# Sheet_1_2024-04-15.net
KiCad netlist of a schematic drawn in Altium Designer
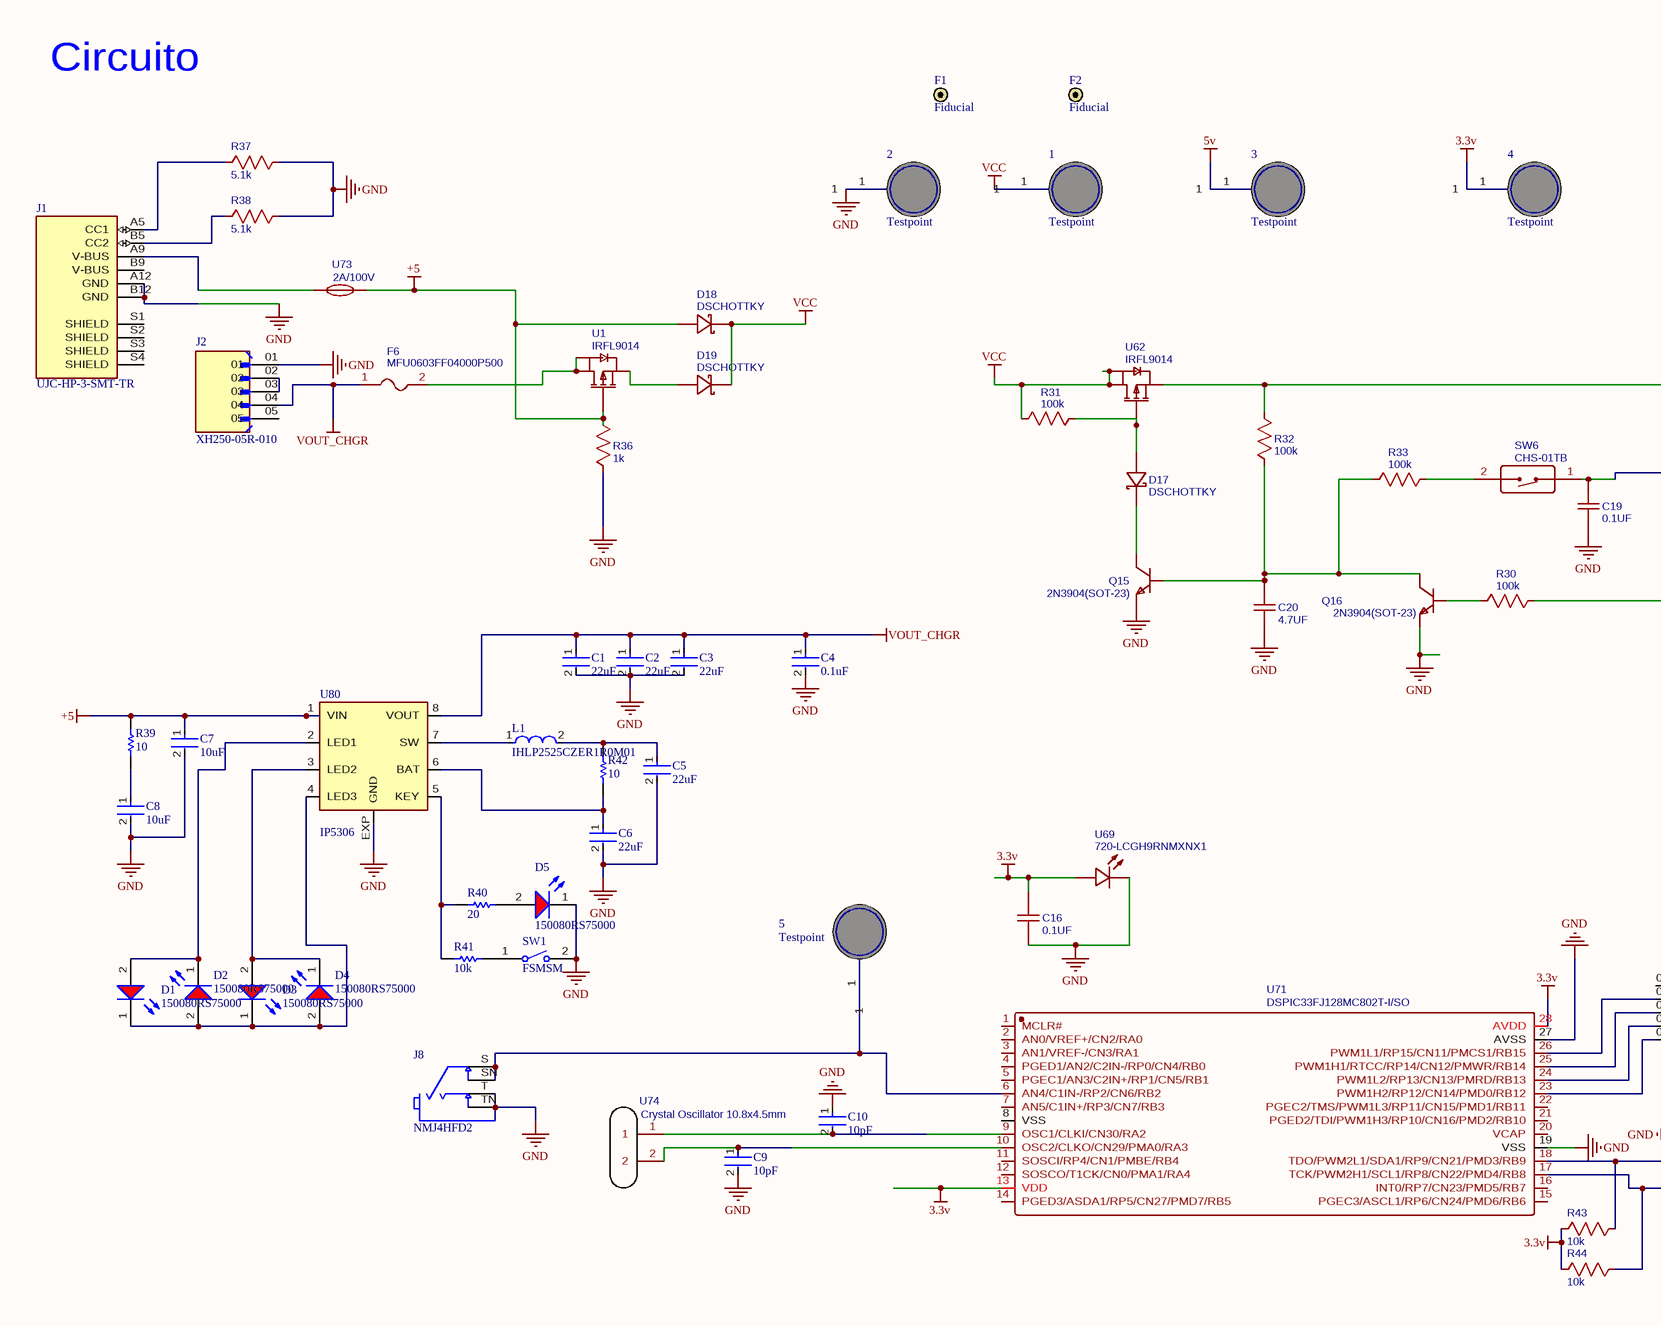
[diagram p0: Sheet_1_2024-04-15.schdoc, left]
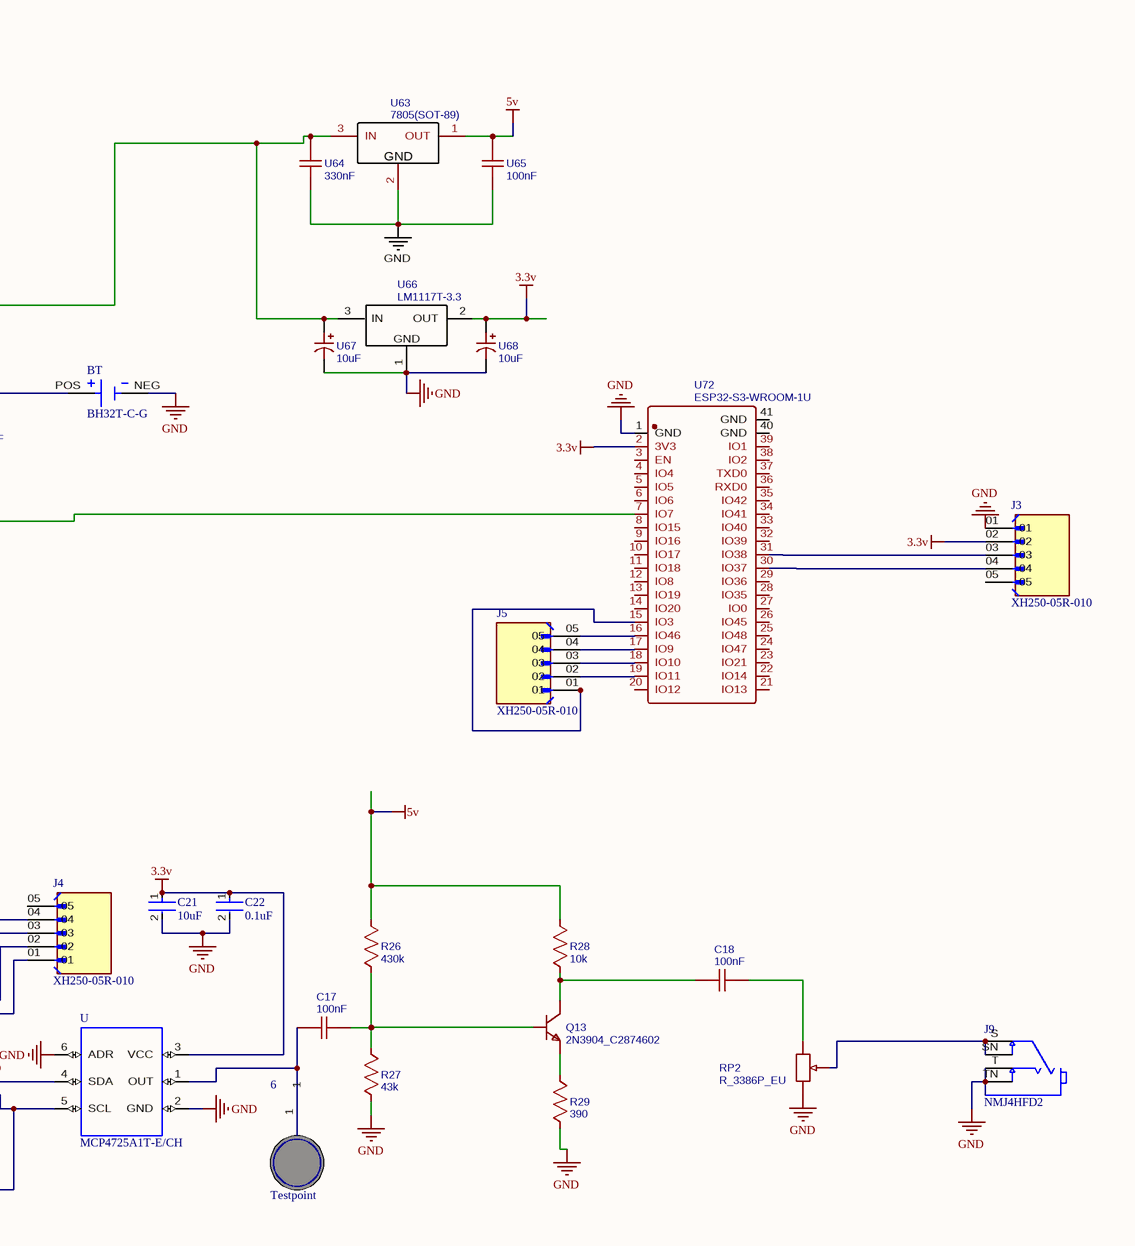
[diagram p1: Sheet_1_2024-04-15.schdoc, right]

(export (version "E")
  (design (tool "Eeschema 10.0.6"))
  (components
    (comp (ref "1")
      (value "Testpoint")
      (footprint "TestPoint")
      (libsource (lib "Schlib1") (part "Testpoint"))
    )
    (comp (ref "2")
      (value "Testpoint")
      (footprint "TestPoint")
      (libsource (lib "Schlib1") (part "Testpoint"))
    )
    (comp (ref "3")
      (value "Testpoint")
      (footprint "TestPoint")
      (libsource (lib "Schlib1") (part "Testpoint"))
    )
    (comp (ref "4")
      (value "Testpoint")
      (footprint "TestPoint")
      (libsource (lib "Schlib1") (part "Testpoint"))
    )
    (comp (ref "5")
      (value "Testpoint")
      (footprint "TestPoint")
      (libsource (lib "Schlib1") (part "Testpoint"))
    )
    (comp (ref "6")
      (value "Testpoint")
      (footprint "TestPoint")
      (libsource (lib "Schlib1") (part "Testpoint"))
    )
    (comp (ref "BT")
      (value "BH32T-C-G")
      (footprint "PcbLib1:BAT_BH32T-C-G")
      (description "BATTERY HOLDER COIN 20MM PC PIN")
      (fields (field (name "MF") "MPD"))
      (libsource (lib "Schlib1") (part "BH32T-C-G"))
    )
    (comp (ref "C1")
      (value "22uF")
      (footprint "FP-C0805C-DN-MFG")
      (description "Capacitor; Ceramic; Cap; 22.0pF; Tol 5%; SMT; Vol-Rtg 50V; C0G; Tape and Reel")
      (fields
        (field (name "OCTOPART") "https://octopart.com/c0805c220j5gactu-kemet-145470")
        (field (name "MANUFACTURER") "KEMET")
      )
      (libsource (lib "Altium Content Vault") (part "b4654b650e69147ec39a6b967a45e02"))
    )
    (comp (ref "C2")
      (value "22uF")
      (footprint "FP-C0805C-DN-MFG")
      (description "Capacitor; Ceramic; Cap; 22.0pF; Tol 5%; SMT; Vol-Rtg 50V; C0G; Tape and Reel")
      (fields
        (field (name "OCTOPART") "https://octopart.com/c0805c220j5gactu-kemet-145470")
        (field (name "MANUFACTURER") "KEMET")
      )
      (libsource (lib "Altium Content Vault") (part "b4654b650e69147ec39a6b967a45e02"))
    )
    (comp (ref "C3")
      (value "22uF")
      (footprint "FP-C0805C-DN-MFG")
      (description "Capacitor; Ceramic; Cap; 22.0pF; Tol 5%; SMT; Vol-Rtg 50V; C0G; Tape and Reel")
      (fields
        (field (name "OCTOPART") "https://octopart.com/c0805c220j5gactu-kemet-145470")
        (field (name "MANUFACTURER") "KEMET")
      )
      (libsource (lib "Altium Content Vault") (part "b4654b650e69147ec39a6b967a45e02"))
    )
    (comp (ref "C4")
      (value "0.1uF")
      (footprint "FP-C0805C-DN-MFG")
      (description "Capacitor; Ceramic; Cap; 22.0pF; Tol 5%; SMT; Vol-Rtg 50V; C0G; Tape and Reel")
      (fields
        (field (name "OCTOPART") "https://octopart.com/c0805c220j5gactu-kemet-145470")
        (field (name "MANUFACTURER") "KEMET")
      )
      (libsource (lib "Altium Content Vault") (part "b4654b650e69147ec39a6b967a45e02"))
    )
    (comp (ref "C5")
      (value "22uF")
      (footprint "FP-C0805C-DN-MFG")
      (description "Capacitor; Ceramic; Cap; 22.0pF; Tol 5%; SMT; Vol-Rtg 50V; C0G; Tape and Reel")
      (fields
        (field (name "OCTOPART") "https://octopart.com/c0805c220j5gactu-kemet-145470")
        (field (name "MANUFACTURER") "KEMET")
      )
      (libsource (lib "Altium Content Vault") (part "b4654b650e69147ec39a6b967a45e02"))
    )
    (comp (ref "C6")
      (value "22uF")
      (footprint "FP-C0805C-DN-MFG")
      (description "Capacitor; Ceramic; Cap; 22.0pF; Tol 5%; SMT; Vol-Rtg 50V; C0G; Tape and Reel")
      (fields
        (field (name "OCTOPART") "https://octopart.com/c0805c220j5gactu-kemet-145470")
        (field (name "MANUFACTURER") "KEMET")
      )
      (libsource (lib "Altium Content Vault") (part "b4654b650e69147ec39a6b967a45e02"))
    )
    (comp (ref "C7")
      (value "10uF")
      (footprint "FP-C0805C-DN-MFG")
      (description "Capacitor; Ceramic; Cap; 22.0pF; Tol 5%; SMT; Vol-Rtg 50V; C0G; Tape and Reel")
      (fields
        (field (name "OCTOPART") "https://octopart.com/c0805c220j5gactu-kemet-145470")
        (field (name "MANUFACTURER") "KEMET")
      )
      (libsource (lib "Altium Content Vault") (part "b4654b650e69147ec39a6b967a45e02"))
    )
    (comp (ref "C8")
      (value "10uF")
      (footprint "FP-C0805C-DN-MFG")
      (description "Capacitor; Ceramic; Cap; 22.0pF; Tol 5%; SMT; Vol-Rtg 50V; C0G; Tape and Reel")
      (fields
        (field (name "OCTOPART") "https://octopart.com/c0805c220j5gactu-kemet-145470")
        (field (name "MANUFACTURER") "KEMET")
      )
      (libsource (lib "Altium Content Vault") (part "b4654b650e69147ec39a6b967a45e02"))
    )
    (comp (ref "C9")
      (value "10pF")
      (footprint "FP-C0805C-DN-MFG")
      (description "Capacitor; Ceramic; Cap; 22.0pF; Tol 5%; SMT; Vol-Rtg 50V; C0G; Tape and Reel")
      (fields
        (field (name "OCTOPART") "https://octopart.com/c0805c220j5gactu-kemet-145470")
        (field (name "MANUFACTURER") "KEMET")
      )
      (libsource (lib "Altium Content Vault") (part "b4654b650e69147ec39a6b967a45e02"))
    )
    (comp (ref "C10")
      (value "10pF")
      (footprint "FP-C0805C-DN-MFG")
      (description "Capacitor; Ceramic; Cap; 22.0pF; Tol 5%; SMT; Vol-Rtg 50V; C0G; Tape and Reel")
      (fields
        (field (name "OCTOPART") "https://octopart.com/c0805c220j5gactu-kemet-145470")
        (field (name "MANUFACTURER") "KEMET")
      )
      (libsource (lib "Altium Content Vault") (part "b4654b650e69147ec39a6b967a45e02"))
    )
    (comp (ref "C16")
      (value "0.1UF")
      (footprint "PcbLib1:RESC2012X60N")
      (fields
        (field (name "MANUFACTURER") "ReliaPro")
        (field (name "MANUFACTURER PART") "250V 0.1UF 5% CBBCapacitor")
      )
      (libsource (lib "altium-import") (part "root_1_0.1UF_"))
    )
    (comp (ref "C17")
      (value "100nF")
      (footprint "PcbLib1:RESC2012X60N")
      (fields (field (name "CONTRIBUTOR") "LCEDA_Lib"))
      (libsource (lib "altium-import") (part "root_0_100nF_"))
    )
    (comp (ref "C18")
      (value "100nF")
      (footprint "PcbLib1:RESC2012X60N")
      (fields (field (name "CONTRIBUTOR") "LCEDA_Lib"))
      (libsource (lib "altium-import") (part "root_0_100nF_"))
    )
    (comp (ref "C19")
      (value "0.1UF")
      (footprint "PcbLib1:RESC2012X60N")
      (fields
        (field (name "MANUFACTURER") "ReliaPro")
        (field (name "MANUFACTURER PART") "250V 0.1UF 5% CBBCapacitor")
      )
      (libsource (lib "altium-import") (part "root_1_0.1UF_"))
    )
    (comp (ref "C20")
      (value "4.7UF")
      (footprint "PcbLib1:RESC2012X60N")
      (fields
        (field (name "MANUFACTURER") "ReliaPro")
        (field (name "MANUFACTURER PART") "250V 0.1UF 5% CBBCapacitor")
      )
      (libsource (lib "altium-import") (part "root_1_4.7UF_"))
    )
    (comp (ref "C21")
      (value "10uF")
      (footprint "FP-C0805C-DN-MFG")
      (description "Capacitor; Ceramic; Cap; 22.0pF; Tol 5%; SMT; Vol-Rtg 50V; C0G; Tape and Reel")
      (fields
        (field (name "OCTOPART") "https://octopart.com/c0805c220j5gactu-kemet-145470")
        (field (name "MANUFACTURER") "KEMET")
      )
      (libsource (lib "Altium Content Vault") (part "b4654b650e69147ec39a6b967a45e02"))
    )
    (comp (ref "C22")
      (value "0.1uF")
      (footprint "FP-C0805C-DN-MFG")
      (description "Capacitor; Ceramic; Cap; 22.0pF; Tol 5%; SMT; Vol-Rtg 50V; C0G; Tape and Reel")
      (fields
        (field (name "OCTOPART") "https://octopart.com/c0805c220j5gactu-kemet-145470")
        (field (name "MANUFACTURER") "KEMET")
      )
      (libsource (lib "Altium Content Vault") (part "b4654b650e69147ec39a6b967a45e02"))
    )
    (comp (ref "D1")
      (value "150080RS75000")
      (footprint "WL-SMCW_0805_150080xx75000")
      (libsource (lib "Altium Content Vault") (part "LED_Red_2A-1K"))
    )
    (comp (ref "D2")
      (value "150080RS75000")
      (footprint "WL-SMCW_0805_150080xx75000")
      (libsource (lib "Altium Content Vault") (part "LED_Red_2A-1K"))
    )
    (comp (ref "D3")
      (value "150080RS75000")
      (footprint "WL-SMCW_0805_150080xx75000")
      (libsource (lib "Altium Content Vault") (part "LED_Red_2A-1K"))
    )
    (comp (ref "D4")
      (value "150080RS75000")
      (footprint "WL-SMCW_0805_150080xx75000")
      (libsource (lib "Altium Content Vault") (part "LED_Red_2A-1K"))
    )
    (comp (ref "D5")
      (value "150080RS75000")
      (footprint "WL-SMCW_0805_150080xx75000")
      (libsource (lib "Altium Content Vault") (part "LED_Red_2A-1K"))
    )
    (comp (ref "D17")
      (value "DSCHOTTKY")
      (footprint "PcbLib1:SS34BF")
      (fields (field (name "MANUFACTURER PART") "DSchottky") (field (name "CONTRIBUTOR") "LCSC"))
      (libsource (lib "altium-import") (part "root_1_DSCHOTTKY_"))
    )
    (comp (ref "D18")
      (value "DSCHOTTKY")
      (footprint "PcbLib1:SS34BF")
      (fields (field (name "MANUFACTURER PART") "DSchottky") (field (name "CONTRIBUTOR") "LCSC"))
      (libsource (lib "altium-import") (part "root_2_DSCHOTTKY_"))
    )
    (comp (ref "D19")
      (value "DSCHOTTKY")
      (footprint "PcbLib1:SS34BF")
      (fields (field (name "MANUFACTURER PART") "DSchottky") (field (name "CONTRIBUTOR") "LCSC"))
      (libsource (lib "altium-import") (part "root_2_DSCHOTTKY_"))
    )
    (comp (ref "F1") (value "Fiducial") (footprint "Fiducial") (libsource (lib "Schlib1") (part "Fiducial")))
    (comp (ref "F2") (value "Fiducial") (footprint "Fiducial") (libsource (lib "Schlib1") (part "Fiducial")))
    (comp (ref "F6")
      (value "MFU0603FF04000P500")
      (footprint "PcbLib1:RESC2012X60N")
      (fields (field (name "MANUFACTURER") "VISHAY(威世)") (field (name "CONTRIBUTOR") "LCSC"))
      (libsource (lib "altium-import") (part "root_0_MFU0603FF04000P500_"))
    )
    (comp (ref "J1")
      (value "UJC-HP-3-SMT-TR")
      (footprint "PcbLib1:CUI_UJC-HP-3-SMT-TR")
      (description "Type C, 3 A, Right Angle, Surface Mount (SMT), Power-Only USB Receptacle")
      (libsource (lib "Schlib1") (part "UJC-HP-3-SMT-TR"))
    )
    (comp (ref "J2")
      (value "XH250-05R-010")
      (footprint "PcbLib1:VALCON_XH250-05R-010")
      (description "Valcon Wire-to-Board 2.50mm Straight & Right Angle PCB Connectors")
      (fields (field (name "MF") "Valcon"))
      (libsource (lib "") (part "XH250-05R-010_1"))
    )
    (comp (ref "J3")
      (value "XH250-05R-010")
      (footprint "PcbLib1:VALCON_XH250-05R-010 - duplicate")
      (description "Valcon Wire-to-Board 2.50mm Straight & Right Angle PCB Connectors")
      (fields (field (name "MF") "Valcon"))
      (libsource (lib "") (part "XH250-05R-010_2"))
    )
    (comp (ref "J4")
      (value "XH250-05R-010")
      (footprint "PcbLib1:VALCON_XH250-05R-010 - duplicate - duplicate")
      (description "Valcon Wire-to-Board 2.50mm Straight & Right Angle PCB Connectors")
      (fields (field (name "MF") "Valcon"))
      (libsource (lib "") (part "XH250-05R-010_3"))
    )
    (comp (ref "J5")
      (value "XH250-05R-010")
      (footprint "PcbLib1:VALCON_XH250-05R-010 - duplicate")
      (description "Valcon Wire-to-Board 2.50mm Straight & Right Angle PCB Connectors")
      (fields (field (name "MF") "Valcon"))
      (libsource (lib "Schlib1") (part "XH250-05R-010"))
    )
    (comp (ref "J8")
      (value "NMJ4HFD2")
      (footprint "NEUTRIK_NMJ4HFD2")
      (description "1/4 mono jack, switched, with a full threaded nose and straight PCB pins, mounting nut included")
      (fields (field (name "MF") "Neutrik"))
      (libsource (lib "Schlib1") (part "NMJ4HFD2"))
    )
    (comp (ref "J9")
      (value "NMJ4HFD2")
      (footprint "NEUTRIK_NMJ4HFD2")
      (description "1/4 mono jack, switched, with a full threaded nose and straight PCB pins, mounting nut included")
      (fields (field (name "MF") "Neutrik"))
      (libsource (lib "Schlib1") (part "NMJ4HFD2"))
    )
    (comp (ref "L1")
      (value "IHLP2525CZER1R0M01")
      (footprint "FP-IHLP-2525CZ-FP_2_413x3-MFG")
      (description "Commercial Inductors, High Saturation Series 1uH 11A 10mΩ 20%")
      (fields (field (name "TOLERANCE") "20%"))
      (libsource (lib "Altium Content Vault") (part "725321dda6339637d4d059423bc1c3c"))
    )
    (comp (ref "Q13")
      (value "2N3904_C2874602")
      (footprint "PcbLib1:TO92127P495H495-3")
      (fields
        (field (name "MANUFACTURER") "JSMSEMI(杰盛微)")
        (field (name "MANUFACTURER PART") "2N3904")
        (field (name "CONTRIBUTOR") "LCSC")
      )
      (libsource (lib "altium-import") (part "root_0_2N3904_C2874602_"))
    )
    (comp (ref "Q15")
      (value "2N3904(SOT-23)")
      (footprint "PcbLib1:TO92127P495H495-3")
      (fields
        (field (name "MANUFACTURER") "KEC")
        (field (name "MANUFACTURER PART") "2n3904S-RTK/PS")
        (field (name "CONTRIBUTOR") "LCEDA_Lib")
      )
      (libsource (lib "altium-import") (part "root_0_2N3904(SOT-23)_"))
    )
    (comp (ref "Q16")
      (value "2N3904(SOT-23)")
      (footprint "PcbLib1:TO92127P495H495-3 - duplicate")
      (fields
        (field (name "MANUFACTURER") "KEC")
        (field (name "MANUFACTURER PART") "2n3904S-RTK/PS")
        (field (name "CONTRIBUTOR") "LCEDA_Lib")
      )
      (libsource (lib "altium-import") (part "root_0_2N3904(SOT-23)_"))
    )
    (comp (ref "R26")
      (value "430k")
      (footprint "PcbLib1:RESC2012X60N")
      (fields (field (name "CONTRIBUTOR") "LCEDA_Lib"))
      (libsource (lib "altium-import") (part "root_1_430k_"))
    )
    (comp (ref "R27")
      (value "43k")
      (footprint "PcbLib1:RESC2012X60N")
      (fields (field (name "CONTRIBUTOR") "LCEDA_Lib"))
      (libsource (lib "altium-import") (part "root_1_43k_"))
    )
    (comp (ref "R28")
      (value "10k")
      (footprint "PcbLib1:RESC2012X60N")
      (fields (field (name "CONTRIBUTOR") "LCEDA_Lib"))
      (libsource (lib "altium-import") (part "root_1_10k_"))
    )
    (comp (ref "R29")
      (value "390")
      (footprint "PcbLib1:RESC2012X60N")
      (fields (field (name "CONTRIBUTOR") "LCEDA_Lib"))
      (libsource (lib "altium-import") (part "root_1_390_"))
    )
    (comp (ref "R30")
      (value "100k")
      (footprint "PcbLib1:RESC2012X60N")
      (fields (field (name "CONTRIBUTOR") "LCEDA_Lib"))
      (libsource (lib "altium-import") (part "root_0_100k_"))
    )
    (comp (ref "R31")
      (value "100k")
      (footprint "PcbLib1:RESC2012X60N")
      (fields (field (name "CONTRIBUTOR") "LCEDA_Lib"))
      (libsource (lib "altium-import") (part "root_2_100k_"))
    )
    (comp (ref "R32")
      (value "100k")
      (footprint "PcbLib1:RESC2012X60N")
      (fields (field (name "CONTRIBUTOR") "LCEDA_Lib"))
      (libsource (lib "altium-import") (part "root_3_100k_"))
    )
    (comp (ref "R33")
      (value "100k")
      (footprint "PcbLib1:RESC2012X60N")
      (fields (field (name "CONTRIBUTOR") "LCEDA_Lib"))
      (libsource (lib "altium-import") (part "root_0_100k_"))
    )
    (comp (ref "R36")
      (value "1k")
      (footprint "PcbLib1:RESC2012X60N")
      (fields (field (name "CONTRIBUTOR") "LCEDA_Lib"))
      (libsource (lib "altium-import") (part "root_3_1k_"))
    )
    (comp (ref "R37")
      (value "5.1k")
      (footprint "PcbLib1:RESC2012X60N")
      (fields (field (name "CONTRIBUTOR") "LCEDA_Lib"))
      (libsource (lib "altium-import") (part "root_0_1k_"))
    )
    (comp (ref "R38")
      (value "5.1k")
      (footprint "PcbLib1:RESC2012X60N")
      (fields (field (name "CONTRIBUTOR") "LCEDA_Lib"))
      (libsource (lib "altium-import") (part "root_0_1k_"))
    )
    (comp (ref "R39")
      (value "10")
      (footprint "RESC2013X50X30LL20T20")
      (fields (field (name "MANUFACTURER") "Vishay Dale") (field (name "PART NUMBER") "CRCW08050000Z0EA"))
      (libsource (lib "Altium Content Vault") (part "RES"))
    )
    (comp (ref "R40")
      (value "20")
      (footprint "RESC2013X50X30LL20T20")
      (fields (field (name "MANUFACTURER") "Vishay Dale") (field (name "PART NUMBER") "CRCW08050000Z0EA"))
      (libsource (lib "Altium Content Vault") (part "RES"))
    )
    (comp (ref "R41")
      (value "10k")
      (footprint "RESC2013X50X30LL20T20")
      (fields (field (name "MANUFACTURER") "Vishay Dale") (field (name "PART NUMBER") "CRCW08050000Z0EA"))
      (libsource (lib "Altium Content Vault") (part "RES"))
    )
    (comp (ref "R42")
      (value "10")
      (footprint "RESC2013X50X30LL20T20")
      (fields (field (name "MANUFACTURER") "Vishay Dale") (field (name "PART NUMBER") "CRCW08050000Z0EA"))
      (libsource (lib "Altium Content Vault") (part "RES"))
    )
    (comp (ref "R43")
      (value "10k")
      (footprint "PcbLib1:RESC2012X60N")
      (fields (field (name "CONTRIBUTOR") "LCEDA_Lib"))
      (libsource (lib "altium-import") (part "root_2_43k_"))
    )
    (comp (ref "R44")
      (value "10k")
      (footprint "PcbLib1:RESC2012X60N")
      (fields (field (name "CONTRIBUTOR") "LCEDA_Lib"))
      (libsource (lib "altium-import") (part "root_2_43k_"))
    )
    (comp (ref "RP2")
      (value "R_3386P_EU")
      (footprint "PcbLib1:TRIM_3386P-1-101TLF")
      (fields (field (name "CONTRIBUTOR") "LCEDA_Lib"))
      (libsource (lib "altium-import") (part "root_3_R_3386P_EU_"))
    )
    (comp (ref "SW1")
      (value "FSMSM")
      (footprint "TECO-FSMSM-2_V")
      (description "FSMSM Push Button Switch, 50 mA, -35 to 85 degC, 2-Pin SMD, RoHS, Bulk")
      (fields (field (name "MANUFACTURER") "TE Connectivity"))
      (libsource (lib "Altium Content Vault") (part "SW-SPST-2_C"))
    )
    (comp (ref "SW6")
      (value "CHS-01TB")
      (footprint "PcbLib1:SW_TS09-63-25-R-260-SMT-TR")
      (fields (field (name "MANUFACTURER") "NIDEC(尼得科)") (field (name "CONTRIBUTOR") "LCSC"))
      (libsource (lib "altium-import") (part "root_2_CHS-01TB_"))
    )
    (comp (ref "U")
      (value "MCP4725A1T-E/CH")
      (footprint "PcbLib1:SOT23-6")
      (description "12 Bit Digital to Analog Converter 1 SOT-23-6")
      (fields (field (name "MF") "Microchip"))
      (libsource (lib "Schlib1") (part "MCP4725A1T-E/CH"))
    )
    (comp (ref "U1")
      (value "IRFL9014")
      (footprint "PcbLib1:IRFL9014")
      (fields (field (name "MANUFACTURER") "TECH PUBLIC(台舟)") (field (name "CONTRIBUTOR") "lcsc"))
      (libsource (lib "altium-import") (part "root_1_IRFL9014_"))
    )
    (comp (ref "U62")
      (value "IRFL9014")
      (footprint "PcbLib1:IRFL9014")
      (fields (field (name "MANUFACTURER") "TECH PUBLIC(台舟)") (field (name "CONTRIBUTOR") "lcsc"))
      (libsource (lib "altium-import") (part "root_1_IRFL9014_"))
    )
    (comp (ref "U63")
      (value "7805(SOT-89)")
      (footprint "PcbLib1:TO254P1054X470X2600-3")
      (fields
        (field (name "MANUFACTURER") "CJ")
        (field (name "MANUFACTURER PART") "CJ78L05")
        (field (name "CONTRIBUTOR") "LCEDA_Lib")
      )
      (libsource (lib "altium-import") (part "root_0_7805(SOT-89)_"))
    )
    (comp (ref "U64")
      (value "330nF")
      (footprint "PcbLib1:RESC2012X60N")
      (fields
        (field (name "MANUFACTURER") "TDK")
        (field (name "MANUFACTURER PART") "B32560J3334K000")
        (field (name "CONTRIBUTOR") "lcsc")
      )
      (libsource (lib "altium-import") (part "root_1_330nF_"))
    )
    (comp (ref "U65")
      (value "100nF")
      (footprint "PcbLib1:RESC2012X60N")
      (fields
        (field (name "MANUFACTURER") "TDK")
        (field (name "MANUFACTURER PART") "B32560J3334K000")
        (field (name "CONTRIBUTOR") "lcsc")
      )
      (libsource (lib "altium-import") (part "root_1_100nF_"))
    )
    (comp (ref "U66")
      (value "LM1117T-3.3")
      (footprint "PcbLib1:TO254P1054X470X1955-3")
      (fields (field (name "MANUFACTURER") "HGSEMI(华冠)") (field (name "CONTRIBUTOR") "LCSC"))
      (libsource (lib "altium-import") (part "root_0_LM1117T-3.3_"))
    )
    (comp (ref "U67")
      (value "10uF")
      (footprint "PcbLib1:CAP_EEEHB1H100P")
      (fields
        (field (name "MANUFACTURER") "Kyocera AVX")
        (field (name "MANUFACTURER PART") "F980J106MMA")
        (field (name "CONTRIBUTOR") "lcsc")
      )
      (libsource (lib "altium-import") (part "root_3_10uF_"))
    )
    (comp (ref "U68")
      (value "10uF")
      (footprint "PcbLib1:CAP_EEEHB1H100P")
      (fields
        (field (name "MANUFACTURER") "Kyocera AVX")
        (field (name "MANUFACTURER PART") "F980J106MMA")
        (field (name "CONTRIBUTOR") "lcsc")
      )
      (libsource (lib "altium-import") (part "root_3_10uF_"))
    )
    (comp (ref "U69")
      (value "720-LCGH9RNMXNX1")
      (footprint "PcbLib1:RESC2012X60N")
      (fields (field (name "CONTRIBUTOR") "lcsc"))
      (libsource (lib "altium-import") (part "root_0_720-LCGH9RNMXNX1_"))
    )
    (comp (ref "U71")
      (value "DSPIC33FJ128MC802T-I/SO")
      (footprint "PcbLib1:OST_ED281DT")
      (fields
        (field (name "MANUFACTURER") "MICROCHIP(美国微芯)")
        (field (name "MANUFACTURER PART") "dsPIC33FJ128MC802T-I/SO")
        (field (name "CONTRIBUTOR") "lcsc")
      )
      (libsource (lib "altium-import") (part "root_0_DSPIC33FJ128MC802T-I/SO_"))
    )
    (comp (ref "U72")
      (value "ESP32-S3-WROOM-1U")
      (footprint "PcbLib1:MODULE_ESP32-DEVKITC")
      (fields (field (name "CONTRIBUTOR") "lcsc"))
      (libsource (lib "altium-import") (part "root_0_ESP32-S3-WROOM-1U_"))
    )
    (comp (ref "U73")
      (value "2A/100V")
      (footprint "PcbLib1:RESC2012X60N")
      (fields (field (name "MANUFACTURER PART") "20A/100V") (field (name "CONTRIBUTOR") "lcsc"))
      (libsource (lib "altium-import") (part "root_0_2A/100V_"))
    )
    (comp (ref "U74")
      (value "Crystal Oscillator 10.8x4.5mm")
      (footprint "PcbLib1:XTAL_ECS-400-20-46X")
      (fields (field (name "CONTRIBUTOR") "colebenedicto"))
      (libsource (lib "altium-import") (part "root_0_Crystal Oscillator 10.8x4.5mm_"))
    )
    (comp (ref "U80")
      (value "IP5306")
      (footprint "PcbLib1:SOP8-P")
      (description "RC (Pi) EMI Filter 2nd Order Low Pass 2 Channel R = 2.2kOhms, C = 1700pF 8-UFBGA, WLCSP")
      (fields (field (name "MF") "NXP USA Inc."))
      (libsource (lib "Schlib1") (part "IP5306"))
    )
  )
  (nets
    (net (code "1") (name "+5") (class "Default")
      (node (ref "C7") (pin "1") (pinfunction "1_1") (pintype "passive"))
      (node (ref "D18") (pin "2") (pinfunction "2_2") (pintype "passive"))
      (node (ref "R36") (pin "1") (pinfunction "1_1") (pintype "passive"))
      (node (ref "R39") (pin "2") (pinfunction "2_2") (pintype "passive"))
      (node (ref "U1") (pin "1") (pinfunction "G_1") (pintype "passive"))
      (node (ref "U73") (pin "2") (pinfunction "2_2") (pintype "passive"))
      (node (ref "U80") (pin "1") (pinfunction "VIN_1") (pintype "bidirectional"))
    )
    (net (code "2") (name "3.3v") (class "Default")
      (node (ref "4") (pin "1") (pinfunction "1_1") (pintype "passive"))
      (node (ref "C16") (pin "2") (pinfunction "2_2") (pintype "passive"))
      (node (ref "C21") (pin "1") (pinfunction "1_1") (pintype "passive"))
      (node (ref "C22") (pin "1") (pinfunction "1_1") (pintype "passive"))
      (node (ref "J3") (pin "02") (pinfunction "02_02") (pintype "passive"))
      (node (ref "R43") (pin "2") (pinfunction "2_2") (pintype "passive"))
      (node (ref "R44") (pin "2") (pinfunction "2_2") (pintype "passive"))
      (node (ref "U") (pin "3") (pinfunction "VCC_3") (pintype "bidirectional"))
      (node (ref "U66") (pin "2") (pinfunction "OUT_2") (pintype "passive"))
      (node (ref "U68") (pin "1") (pinfunction "1_1") (pintype "passive"))
      (node (ref "U69") (pin "2") (pinfunction "A_2") (pintype "passive"))
      (node (ref "U71") (pin "13") (pinfunction "VDD_13") (pintype "passive"))
      (node (ref "U71") (pin "28") (pinfunction "AVDD_28") (pintype "passive"))
      (node (ref "U72") (pin "2") (pinfunction "3V3_2") (pintype "passive"))
    )
    (net (code "3") (name "5v") (class "Default")
      (node (ref "3") (pin "1") (pinfunction "1_1") (pintype "passive"))
      (node (ref "R26") (pin "2") (pinfunction "2_2") (pintype "passive"))
      (node (ref "R28") (pin "2") (pinfunction "2_2") (pintype "passive"))
      (node (ref "U63") (pin "1") (pinfunction "OUT_1") (pintype "passive"))
      (node (ref "U65") (pin "2") (pinfunction "2_2") (pintype "passive"))
    )
    (net (code "4") (name "GND") (class "Default")
      (node (ref "2") (pin "1") (pinfunction "1_1") (pintype "passive"))
      (node (ref "BT") (pin "NEG") (pinfunction "NEG_NEG") (pintype "passive"))
      (node (ref "C1") (pin "2") (pinfunction "2_2") (pintype "passive"))
      (node (ref "C10") (pin "1") (pinfunction "1_1") (pintype "passive"))
      (node (ref "C16") (pin "1") (pinfunction "1_1") (pintype "passive"))
      (node (ref "C19") (pin "1") (pinfunction "1_1") (pintype "passive"))
      (node (ref "C2") (pin "2") (pinfunction "2_2") (pintype "passive"))
      (node (ref "C20") (pin "1") (pinfunction "1_1") (pintype "passive"))
      (node (ref "C21") (pin "2") (pinfunction "2_2") (pintype "passive"))
      (node (ref "C22") (pin "2") (pinfunction "2_2") (pintype "passive"))
      (node (ref "C3") (pin "2") (pinfunction "2_2") (pintype "passive"))
      (node (ref "C4") (pin "2") (pinfunction "2_2") (pintype "passive"))
      (node (ref "C5") (pin "2") (pinfunction "2_2") (pintype "passive"))
      (node (ref "C6") (pin "2") (pinfunction "2_2") (pintype "passive"))
      (node (ref "C7") (pin "2") (pinfunction "2_2") (pintype "passive"))
      (node (ref "C8") (pin "2") (pinfunction "2_2") (pintype "passive"))
      (node (ref "C9") (pin "2") (pinfunction "2_2") (pintype "passive"))
      (node (ref "D5") (pin "1") (pinfunction "K_1") (pintype "passive"))
      (node (ref "J1") (pin "A12") (pinfunction "GND_A12") (pintype "power_in"))
      (node (ref "J1") (pin "B12") (pinfunction "GND_B12") (pintype "power_in"))
      (node (ref "J2") (pin "01") (pinfunction "01_01") (pintype "passive"))
      (node (ref "J3") (pin "01") (pinfunction "01_01") (pintype "passive"))
      (node (ref "J8") (pin "T") (pinfunction "T_T") (pintype "passive"))
      (node (ref "J8") (pin "TN") (pinfunction "TN_TN") (pintype "passive"))
      (node (ref "J9") (pin "T") (pinfunction "T_T") (pintype "passive"))
      (node (ref "J9") (pin "TN") (pinfunction "TN_TN") (pintype "passive"))
      (node (ref "Q15") (pin "1") (pinfunction "E_1") (pintype "passive"))
      (node (ref "Q16") (pin "1") (pinfunction "E_1") (pintype "passive"))
      (node (ref "R27") (pin "1") (pinfunction "1_1") (pintype "passive"))
      (node (ref "R29") (pin "1") (pinfunction "1_1") (pintype "passive"))
      (node (ref "R36") (pin "2") (pinfunction "2_2") (pintype "passive"))
      (node (ref "R37") (pin "2") (pinfunction "2_2") (pintype "passive"))
      (node (ref "R38") (pin "2") (pinfunction "2_2") (pintype "passive"))
      (node (ref "RP2") (pin "3") (pinfunction "3_3") (pintype "passive"))
      (node (ref "SW1") (pin "2") (pinfunction "2_2") (pintype "passive"))
      (node (ref "U") (pin "2") (pinfunction "GND_2") (pintype "bidirectional"))
      (node (ref "U") (pin "6") (pinfunction "ADR_6") (pintype "bidirectional"))
      (node (ref "U63") (pin "2") (pinfunction "GND_2") (pintype "passive"))
      (node (ref "U64") (pin "1") (pinfunction "1_1") (pintype "passive"))
      (node (ref "U65") (pin "1") (pinfunction "1_1") (pintype "passive"))
      (node (ref "U66") (pin "1") (pinfunction "GND_1") (pintype "passive"))
      (node (ref "U67") (pin "2") (pinfunction "2_2") (pintype "passive"))
      (node (ref "U68") (pin "2") (pinfunction "2_2") (pintype "passive"))
      (node (ref "U69") (pin "1") (pinfunction "K_1") (pintype "passive"))
      (node (ref "U71") (pin "19") (pinfunction "VSS_19") (pintype "passive"))
      (node (ref "U71") (pin "27") (pinfunction "AVSS_27") (pintype "passive"))
      (node (ref "U72") (pin "1") (pinfunction "GND_1") (pintype "passive"))
      (node (ref "U80") (pin "EXP") (pinfunction "GND_EXP") (pintype "bidirectional"))
    )
    (net (code "5") (name "Net-(BT-PadPOS)") (class "Default")
      (node (ref "BT") (pin "POS") (pinfunction "POS_POS") (pintype "passive"))
      (node (ref "C19") (pin "2") (pinfunction "2_2") (pintype "passive"))
      (node (ref "SW6") (pin "1") (pinfunction "1_1") (pintype "passive"))
    )
    (net (code "6") (name "Net-(C5-Pad1)") (class "Default")
      (node (ref "C5") (pin "1") (pinfunction "1_1") (pintype "passive"))
      (node (ref "L1") (pin "2") (pinfunction "2_2") (pintype "passive"))
      (node (ref "R42") (pin "2") (pinfunction "2_2") (pintype "passive"))
    )
    (net (code "7") (name "Net-(C8-Pad1)") (class "Default")
      (node (ref "C8") (pin "1") (pinfunction "1_1") (pintype "passive"))
      (node (ref "R39") (pin "1") (pinfunction "1_1") (pintype "passive"))
    )
    (net (code "8") (name "Net-(C18-Pad2)") (class "Default")
      (node (ref "C18") (pin "2") (pinfunction "2_2") (pintype "passive"))
      (node (ref "RP2") (pin "1") (pinfunction "1_1") (pintype "passive"))
    )
    (net (code "9") (name "Net-(D1-A)") (class "Default")
      (node (ref "D1") (pin "2") (pinfunction "A_2") (pintype "passive"))
      (node (ref "D2") (pin "1") (pinfunction "K_1") (pintype "passive"))
      (node (ref "U80") (pin "2") (pinfunction "LED1_2") (pintype "bidirectional"))
    )
    (net (code "10") (name "Net-(D1-K)") (class "Default")
      (node (ref "D1") (pin "1") (pinfunction "K_1") (pintype "passive"))
      (node (ref "D2") (pin "2") (pinfunction "A_2") (pintype "passive"))
      (node (ref "D3") (pin "1") (pinfunction "K_1") (pintype "passive"))
      (node (ref "D4") (pin "2") (pinfunction "A_2") (pintype "passive"))
      (node (ref "U80") (pin "4") (pinfunction "LED3_4") (pintype "bidirectional"))
    )
    (net (code "11") (name "Net-(D3-A)") (class "Default")
      (node (ref "D3") (pin "2") (pinfunction "A_2") (pintype "passive"))
      (node (ref "D4") (pin "1") (pinfunction "K_1") (pintype "passive"))
      (node (ref "U80") (pin "3") (pinfunction "LED2_3") (pintype "bidirectional"))
    )
    (net (code "12") (name "Net-(D5-A)") (class "Default")
      (node (ref "D5") (pin "2") (pinfunction "A_2") (pintype "passive"))
      (node (ref "R40") (pin "2") (pinfunction "2_2") (pintype "passive"))
    )
    (net (code "13") (name "Net-(F6-Pad2)") (class "Default")
      (node (ref "F6") (pin "2") (pinfunction "2_2") (pintype "passive"))
      (node (ref "U1") (pin "2") (pinfunction "D_2") (pintype "passive"))
      (node (ref "U1") (pin "4") (pinfunction "D_4") (pintype "passive"))
    )
    (net (code "14") (name "Net-(J1-CC1)") (class "Default")
      (node (ref "J1") (pin "A5") (pinfunction "CC1_A5") (pintype "bidirectional"))
      (node (ref "R37") (pin "1") (pinfunction "1_1") (pintype "passive"))
    )
    (net (code "15") (name "Net-(J1-CC2)") (class "Default")
      (node (ref "J1") (pin "B5") (pinfunction "CC2_B5") (pintype "bidirectional"))
      (node (ref "R38") (pin "1") (pinfunction "1_1") (pintype "passive"))
    )
    (net (code "16") (name "Net-(J1-V-BUS-PadA9)") (class "Default")
      (node (ref "J1") (pin "A9") (pinfunction "V-BUS_A9") (pintype "power_in"))
      (node (ref "U73") (pin "1") (pinfunction "1_1") (pintype "passive"))
    )
    (net (code "17") (name "Net-(J2-Pad02)") (class "Default")
      (node (ref "J2") (pin "02") (pinfunction "02_02") (pintype "passive"))
      (node (ref "J2") (pin "03") (pinfunction "03_03") (pintype "passive"))
    )
    (net (code "18") (name "Net-(J9-PadS)") (class "Default")
      (node (ref "J9") (pin "S") (pinfunction "S_S") (pintype "passive"))
      (node (ref "J9") (pin "SN") (pinfunction "SN_SN") (pintype "passive"))
      (node (ref "RP2") (pin "2") (pinfunction "2_2") (pintype "passive"))
    )
    (net (code "19") (name "Net-(Q13-B)") (class "Default")
      (node (ref "C17") (pin "2") (pinfunction "2_2") (pintype "passive"))
      (node (ref "Q13") (pin "2") (pinfunction "B_2") (pintype "passive"))
      (node (ref "R26") (pin "1") (pinfunction "1_1") (pintype "passive"))
      (node (ref "R27") (pin "2") (pinfunction "2_2") (pintype "passive"))
    )
    (net (code "20") (name "Net-(Q13-C)") (class "Default")
      (node (ref "C18") (pin "1") (pinfunction "1_1") (pintype "passive"))
      (node (ref "Q13") (pin "3") (pinfunction "C_3") (pintype "passive"))
      (node (ref "R28") (pin "1") (pinfunction "1_1") (pintype "passive"))
    )
    (net (code "21") (name "Net-(Q13-E)") (class "Default")
      (node (ref "Q13") (pin "1") (pinfunction "E_1") (pintype "passive"))
      (node (ref "R29") (pin "2") (pinfunction "2_2") (pintype "passive"))
    )
    (net (code "22") (name "Net-(Q15-B)") (class "Default")
      (node (ref "C20") (pin "2") (pinfunction "2_2") (pintype "passive"))
      (node (ref "Q15") (pin "2") (pinfunction "B_2") (pintype "passive"))
      (node (ref "Q16") (pin "3") (pinfunction "C_3") (pintype "passive"))
      (node (ref "R32") (pin "2") (pinfunction "2_2") (pintype "passive"))
      (node (ref "R33") (pin "1") (pinfunction "1_1") (pintype "passive"))
    )
    (net (code "23") (name "Net-(Q15-C)") (class "Default")
      (node (ref "D17") (pin "1") (pinfunction "1_1") (pintype "passive"))
      (node (ref "Q15") (pin "3") (pinfunction "C_3") (pintype "passive"))
    )
    (net (code "24") (name "Net-(Q16-B)") (class "Default")
      (node (ref "Q16") (pin "2") (pinfunction "B_2") (pintype "passive"))
      (node (ref "R30") (pin "1") (pinfunction "1_1") (pintype "passive"))
    )
    (net (code "25") (name "Net-(R33-Pad2)") (class "Default")
      (node (ref "R33") (pin "2") (pinfunction "2_2") (pintype "passive"))
      (node (ref "SW6") (pin "2") (pinfunction "2_2") (pintype "passive"))
    )
    (net (code "26") (name "Net-(R41-Pad2)") (class "Default")
      (node (ref "R41") (pin "2") (pinfunction "2_2") (pintype "passive"))
      (node (ref "SW1") (pin "1") (pinfunction "1_1") (pintype "passive"))
    )
    (net (code "27") (name "Net-(U-OUT)") (class "Default")
      (node (ref "6") (pin "1") (pinfunction "1_1") (pintype "passive"))
      (node (ref "C17") (pin "1") (pinfunction "1_1") (pintype "passive"))
      (node (ref "U") (pin "1") (pinfunction "OUT_1") (pintype "bidirectional"))
    )
    (net (code "28") (name "Net-(U-SCL)") (class "Default")
      (node (ref "R44") (pin "1") (pinfunction "1_1") (pintype "passive"))
      (node (ref "U") (pin "5") (pinfunction "SCL_5") (pintype "bidirectional"))
      (node (ref "U71") (pin "17") (pinfunction "TCK/PWM2H1/SCL1/RP8/CN22/PMD4/RB8_17") (pintype "passive"))
    )
    (net (code "29") (name "Net-(U-SDA)") (class "Default")
      (node (ref "R43") (pin "1") (pinfunction "1_1") (pintype "passive"))
      (node (ref "U") (pin "4") (pinfunction "SDA_4") (pintype "bidirectional"))
      (node (ref "U71") (pin "18") (pinfunction "TDO/PWM2L1/SDA1/RP9/CN21/PMD3/RB9_18") (pintype "passive"))
    )
    (net (code "30") (name "Net-(U1-S)") (class "Default")
      (node (ref "D19") (pin "2") (pinfunction "2_2") (pintype "passive"))
      (node (ref "U1") (pin "3") (pinfunction "S_3") (pintype "passive"))
    )
    (net (code "31") (name "Net-(U62-G)") (class "Default")
      (node (ref "D17") (pin "2") (pinfunction "2_2") (pintype "passive"))
      (node (ref "R31") (pin "1") (pinfunction "1_1") (pintype "passive"))
      (node (ref "U62") (pin "1") (pinfunction "G_1") (pintype "passive"))
    )
    (net (code "32") (name "Net-(U62-S)") (class "Default")
      (node (ref "R32") (pin "1") (pinfunction "1_1") (pintype "passive"))
      (node (ref "U62") (pin "3") (pinfunction "S_3") (pintype "passive"))
      (node (ref "U63") (pin "3") (pinfunction "IN_3") (pintype "passive"))
      (node (ref "U64") (pin "2") (pinfunction "2_2") (pintype "passive"))
      (node (ref "U66") (pin "3") (pinfunction "IN_3") (pintype "passive"))
      (node (ref "U67") (pin "1") (pinfunction "1_1") (pintype "passive"))
    )
    (net (code "33") (name "Net-(U71-AN4{slash}C1IN-{slash}RP2{slash}CN6{slash}RB2)") (class "Default")
      (node (ref "5") (pin "1") (pinfunction "1_1") (pintype "passive"))
      (node (ref "J8") (pin "S") (pinfunction "S_S") (pintype "passive"))
      (node (ref "J8") (pin "SN") (pinfunction "SN_SN") (pintype "passive"))
      (node (ref "U71") (pin "6") (pinfunction "AN4/C1IN-/RP2/CN6/RB2_6") (pintype "passive"))
    )
    (net (code "34") (name "Net-(U71-OSC1{slash}CLKI{slash}CN30{slash}RA2)") (class "Default")
      (node (ref "C10") (pin "2") (pinfunction "2_2") (pintype "passive"))
      (node (ref "U71") (pin "9") (pinfunction "OSC1/CLKI/CN30/RA2_9") (pintype "passive"))
      (node (ref "U74") (pin "1") (pinfunction "1_1") (pintype "passive"))
    )
    (net (code "35") (name "Net-(U71-OSC2{slash}CLKO{slash}CN29{slash}PMA0{slash}RA3)") (class "Default")
      (node (ref "C9") (pin "1") (pinfunction "1_1") (pintype "passive"))
      (node (ref "U71") (pin "10") (pinfunction "OSC2/CLKO/CN29/PMA0/RA3_10") (pintype "passive"))
      (node (ref "U74") (pin "2") (pinfunction "2_2") (pintype "passive"))
    )
    (net (code "36") (name "Net-(U71-PWM1H1{slash}RTCC{slash}RP14{slash}CN12{slash}PMWR{slash}RB14)") (class "Default")
      (node (ref "J4") (pin "03") (pinfunction "03_03") (pintype "passive"))
      (node (ref "U71") (pin "25") (pinfunction "PWM1H1/RTCC/RP14/CN12/PMWR/RB14_25") (pintype "passive"))
    )
    (net (code "37") (name "Net-(U71-PWM1H2{slash}RP12{slash}CN14{slash}PMD0{slash}RB12)") (class "Default")
      (node (ref "J4") (pin "01") (pinfunction "01_01") (pintype "passive"))
      (node (ref "U71") (pin "23") (pinfunction "PWM1H2/RP12/CN14/PMD0/RB12_23") (pintype "passive"))
    )
    (net (code "38") (name "Net-(U71-PWM1L1{slash}RP15{slash}CN11{slash}PMCS1{slash}RB15)") (class "Default")
      (node (ref "J4") (pin "04") (pinfunction "04_04") (pintype "passive"))
      (node (ref "U71") (pin "26") (pinfunction "PWM1L1/RP15/CN11/PMCS1/RB15_26") (pintype "passive"))
    )
    (net (code "39") (name "Net-(U71-PWM1L2{slash}RP13{slash}CN13{slash}PMRD{slash}RB13)") (class "Default")
      (node (ref "J4") (pin "02") (pinfunction "02_02") (pintype "passive"))
      (node (ref "U71") (pin "24") (pinfunction "PWM1L2/RP13/CN13/PMRD/RB13_24") (pintype "passive"))
    )
    (net (code "40") (name "Net-(U72-IO3)") (class "Default")
      (node (ref "J5") (pin "01") (pinfunction "01_01") (pintype "passive"))
      (node (ref "U72") (pin "15") (pinfunction "IO3_15") (pintype "passive"))
    )
    (net (code "41") (name "Net-(U72-IO7)") (class "Default")
      (node (ref "R30") (pin "2") (pinfunction "2_2") (pintype "passive"))
      (node (ref "U72") (pin "7") (pinfunction "IO7_7") (pintype "passive"))
    )
    (net (code "42") (name "Net-(U72-IO9)") (class "Default")
      (node (ref "J5") (pin "04") (pinfunction "04_04") (pintype "passive"))
      (node (ref "U72") (pin "17") (pinfunction "IO9_17") (pintype "passive"))
    )
    (net (code "43") (name "Net-(U72-IO10)") (class "Default")
      (node (ref "J5") (pin "03") (pinfunction "03_03") (pintype "passive"))
      (node (ref "U72") (pin "18") (pinfunction "IO10_18") (pintype "passive"))
    )
    (net (code "44") (name "Net-(U72-IO11)") (class "Default")
      (node (ref "J5") (pin "02") (pinfunction "02_02") (pintype "passive"))
      (node (ref "U72") (pin "19") (pinfunction "IO11_19") (pintype "passive"))
    )
    (net (code "45") (name "Net-(U72-IO37)") (class "Default")
      (node (ref "J3") (pin "04") (pinfunction "04_04") (pintype "passive"))
      (node (ref "U72") (pin "30") (pinfunction "IO37_30") (pintype "passive"))
    )
    (net (code "46") (name "Net-(U72-IO38)") (class "Default")
      (node (ref "J3") (pin "03") (pinfunction "03_03") (pintype "passive"))
      (node (ref "U72") (pin "31") (pinfunction "IO38_31") (pintype "passive"))
    )
    (net (code "47") (name "Net-(U72-IO46)") (class "Default")
      (node (ref "J5") (pin "05") (pinfunction "05_05") (pintype "passive"))
      (node (ref "U72") (pin "16") (pinfunction "IO46_16") (pintype "passive"))
    )
    (net (code "48") (name "Net-(U80-BAT)") (class "Default")
      (node (ref "C6") (pin "1") (pinfunction "1_1") (pintype "passive"))
      (node (ref "R42") (pin "1") (pinfunction "1_1") (pintype "passive"))
      (node (ref "U80") (pin "6") (pinfunction "BAT_6") (pintype "bidirectional"))
    )
    (net (code "49") (name "Net-(U80-KEY)") (class "Default")
      (node (ref "R40") (pin "1") (pinfunction "1_1") (pintype "passive"))
      (node (ref "R41") (pin "1") (pinfunction "1_1") (pintype "passive"))
      (node (ref "U80") (pin "5") (pinfunction "KEY_5") (pintype "bidirectional"))
    )
    (net (code "50") (name "Net-(U80-SW)") (class "Default")
      (node (ref "L1") (pin "1") (pinfunction "1_1") (pintype "passive"))
      (node (ref "U80") (pin "7") (pinfunction "SW_7") (pintype "bidirectional"))
    )
    (net (code "51") (name "VCC") (class "Default")
      (node (ref "1") (pin "1") (pinfunction "1_1") (pintype "passive"))
      (node (ref "D18") (pin "1") (pinfunction "1_1") (pintype "passive"))
      (node (ref "D19") (pin "1") (pinfunction "1_1") (pintype "passive"))
      (node (ref "R31") (pin "2") (pinfunction "2_2") (pintype "passive"))
      (node (ref "U62") (pin "2") (pinfunction "D_2") (pintype "passive"))
      (node (ref "U62") (pin "4") (pinfunction "D_4") (pintype "passive"))
    )
    (net (code "52") (name "VOUT_CHGR") (class "Default")
      (node (ref "C1") (pin "1") (pinfunction "1_1") (pintype "passive"))
      (node (ref "C2") (pin "1") (pinfunction "1_1") (pintype "passive"))
      (node (ref "C3") (pin "1") (pinfunction "1_1") (pintype "passive"))
      (node (ref "C4") (pin "1") (pinfunction "1_1") (pintype "passive"))
      (node (ref "F6") (pin "1") (pinfunction "1_1") (pintype "passive"))
      (node (ref "J2") (pin "04") (pinfunction "04_04") (pintype "passive"))
      (node (ref "U80") (pin "8") (pinfunction "VOUT_8") (pintype "bidirectional"))
    )
    (net (code "53") (name "unconnected-(J1-SHIELD-PadS1)") (class "Default")
      (node (ref "J1") (pin "S1") (pinfunction "SHIELD_S1") (pintype "passive"))
    )
    (net (code "54") (name "unconnected-(J1-SHIELD-PadS2)") (class "Default")
      (node (ref "J1") (pin "S2") (pinfunction "SHIELD_S2") (pintype "passive"))
    )
    (net (code "55") (name "unconnected-(J1-SHIELD-PadS3)") (class "Default")
      (node (ref "J1") (pin "S3") (pinfunction "SHIELD_S3") (pintype "passive"))
    )
    (net (code "56") (name "unconnected-(J1-SHIELD-PadS4)") (class "Default")
      (node (ref "J1") (pin "S4") (pinfunction "SHIELD_S4") (pintype "passive"))
    )
    (net (code "57") (name "unconnected-(J1-V-BUS-PadB9)") (class "Default")
      (node (ref "J1") (pin "B9") (pinfunction "V-BUS_B9") (pintype "power_in"))
    )
    (net (code "58") (name "unconnected-(J2-Pad05)") (class "Default")
      (node (ref "J2") (pin "05") (pinfunction "05_05") (pintype "passive"))
    )
    (net (code "59") (name "unconnected-(J3-Pad05)") (class "Default")
      (node (ref "J3") (pin "05") (pinfunction "05_05") (pintype "passive"))
    )
    (net (code "60") (name "unconnected-(J4-Pad05)") (class "Default")
      (node (ref "J4") (pin "05") (pinfunction "05_05") (pintype "passive"))
    )
    (net (code "61") (name "unconnected-(U71-AN0{slash}VREF+{slash}CN2{slash}RA0-Pad2)") (class "Default")
      (node (ref "U71") (pin "2") (pinfunction "AN0/VREF+/CN2/RA0_2") (pintype "passive"))
    )
    (net (code "62") (name "unconnected-(U71-AN1{slash}VREF-{slash}CN3{slash}RA1-Pad3)") (class "Default")
      (node (ref "U71") (pin "3") (pinfunction "AN1/VREF-/CN3/RA1_3") (pintype "passive"))
    )
    (net (code "63") (name "unconnected-(U71-AN5{slash}C1IN+{slash}RP3{slash}CN7{slash}RB3-Pad7)") (class "Default")
      (node (ref "U71") (pin "7") (pinfunction "AN5/C1IN+/RP3/CN7/RB3_7") (pintype "passive"))
    )
    (net (code "64") (name "unconnected-(U71-INT0{slash}RP7{slash}CN23{slash}PMD5{slash}RB7-Pad16)") (class "Default")
      (node (ref "U71") (pin "16") (pinfunction "INT0/RP7/CN23/PMD5/RB7_16") (pintype "passive"))
    )
    (net (code "65") (name "unconnected-(U71-MCLR#-Pad1)") (class "Default")
      (node (ref "U71") (pin "1") (pinfunction "MCLR#_1") (pintype "passive"))
    )
    (net (code "66") (name "unconnected-(U71-PGEC1{slash}AN3{slash}C2IN+{slash}RP1{slash}CN5{slash}RB1-Pad5)") (class "Default")
      (node (ref "U71") (pin "5") (pinfunction "PGEC1/AN3/C2IN+/RP1/CN5/RB1_5") (pintype "passive"))
    )
    (net (code "67") (name "unconnected-(U71-PGEC2{slash}TMS{slash}PWM1L3{slash}RP11{slash}CN15{slash}PMD1{slash}RB11-Pad22)") (class "Default")
      (node (ref "U71") (pin "22") (pinfunction "PGEC2/TMS/PWM1L3/RP11/CN15/PMD1/RB11_22") (pintype "passive"))
    )
    (net (code "68") (name "unconnected-(U71-PGEC3{slash}ASCL1{slash}RP6{slash}CN24{slash}PMD6{slash}RB6-Pad15)") (class "Default")
      (node (ref "U71") (pin "15") (pinfunction "PGEC3/ASCL1/RP6/CN24/PMD6/RB6_15") (pintype "passive"))
    )
    (net (code "69") (name "unconnected-(U71-PGED1{slash}AN2{slash}C2IN-{slash}RP0{slash}CN4{slash}RB0-Pad4)") (class "Default")
      (node (ref "U71") (pin "4") (pinfunction "PGED1/AN2/C2IN-/RP0/CN4/RB0_4") (pintype "passive"))
    )
    (net (code "70") (name "unconnected-(U71-PGED2{slash}TDI{slash}PWM1H3{slash}RP10{slash}CN16{slash}PMD2{slash}RB10-Pad21)") (class "Default")
      (node (ref "U71") (pin "21") (pinfunction "PGED2/TDI/PWM1H3/RP10/CN16/PMD2/RB10_21") (pintype "passive"))
    )
    (net (code "71") (name "unconnected-(U71-PGED3{slash}ASDA1{slash}RP5{slash}CN27{slash}PMD7{slash}RB5-Pad14)") (class "Default")
      (node (ref "U71") (pin "14") (pinfunction "PGED3/ASDA1/RP5/CN27/PMD7/RB5_14") (pintype "passive"))
    )
    (net (code "72") (name "unconnected-(U71-SOSCI{slash}RP4{slash}CN1{slash}PMBE{slash}RB4-Pad11)") (class "Default")
      (node (ref "U71") (pin "11") (pinfunction "SOSCI/RP4/CN1/PMBE/RB4_11") (pintype "passive"))
    )
    (net (code "73") (name "unconnected-(U71-SOSCO{slash}T1CK{slash}CN0{slash}PMA1{slash}RA4-Pad12)") (class "Default")
      (node (ref "U71") (pin "12") (pinfunction "SOSCO/T1CK/CN0/PMA1/RA4_12") (pintype "passive"))
    )
    (net (code "74") (name "unconnected-(U71-VCAP-Pad20)") (class "Default")
      (node (ref "U71") (pin "20") (pinfunction "VCAP_20") (pintype "passive"))
    )
    (net (code "75") (name "unconnected-(U71-VSS-Pad8)") (class "Default")
      (node (ref "U71") (pin "8") (pinfunction "VSS_8") (pintype "passive"))
    )
    (net (code "76") (name "unconnected-(U72-EN-Pad3)") (class "Default")
      (node (ref "U72") (pin "3") (pinfunction "EN_3") (pintype "passive"))
    )
    (net (code "77") (name "unconnected-(U72-GND-Pad40)") (class "Default")
      (node (ref "U72") (pin "40") (pinfunction "GND_40") (pintype "passive"))
    )
    (net (code "78") (name "unconnected-(U72-GND-Pad41)") (class "Default")
      (node (ref "U72") (pin "41") (pinfunction "GND_41") (pintype "passive"))
    )
    (net (code "79") (name "unconnected-(U72-IO0-Pad27)") (class "Default")
      (node (ref "U72") (pin "27") (pinfunction "IO0_27") (pintype "passive"))
    )
    (net (code "80") (name "unconnected-(U72-IO1-Pad39)") (class "Default")
      (node (ref "U72") (pin "39") (pinfunction "IO1_39") (pintype "passive"))
    )
    (net (code "81") (name "unconnected-(U72-IO2-Pad38)") (class "Default")
      (node (ref "U72") (pin "38") (pinfunction "IO2_38") (pintype "passive"))
    )
    (net (code "82") (name "unconnected-(U72-IO4-Pad4)") (class "Default")
      (node (ref "U72") (pin "4") (pinfunction "IO4_4") (pintype "passive"))
    )
    (net (code "83") (name "unconnected-(U72-IO5-Pad5)") (class "Default")
      (node (ref "U72") (pin "5") (pinfunction "IO5_5") (pintype "passive"))
    )
    (net (code "84") (name "unconnected-(U72-IO6-Pad6)") (class "Default")
      (node (ref "U72") (pin "6") (pinfunction "IO6_6") (pintype "passive"))
    )
    (net (code "85") (name "unconnected-(U72-IO8-Pad12)") (class "Default")
      (node (ref "U72") (pin "12") (pinfunction "IO8_12") (pintype "passive"))
    )
    (net (code "86") (name "unconnected-(U72-IO12-Pad20)") (class "Default")
      (node (ref "U72") (pin "20") (pinfunction "IO12_20") (pintype "passive"))
    )
    (net (code "87") (name "unconnected-(U72-IO13-Pad21)") (class "Default")
      (node (ref "U72") (pin "21") (pinfunction "IO13_21") (pintype "passive"))
    )
    (net (code "88") (name "unconnected-(U72-IO14-Pad22)") (class "Default")
      (node (ref "U72") (pin "22") (pinfunction "IO14_22") (pintype "passive"))
    )
    (net (code "89") (name "unconnected-(U72-IO15-Pad8)") (class "Default")
      (node (ref "U72") (pin "8") (pinfunction "IO15_8") (pintype "passive"))
    )
    (net (code "90") (name "unconnected-(U72-IO16-Pad9)") (class "Default")
      (node (ref "U72") (pin "9") (pinfunction "IO16_9") (pintype "passive"))
    )
    (net (code "91") (name "unconnected-(U72-IO17-Pad10)") (class "Default")
      (node (ref "U72") (pin "10") (pinfunction "IO17_10") (pintype "passive"))
    )
    (net (code "92") (name "unconnected-(U72-IO18-Pad11)") (class "Default")
      (node (ref "U72") (pin "11") (pinfunction "IO18_11") (pintype "passive"))
    )
    (net (code "93") (name "unconnected-(U72-IO19-Pad13)") (class "Default")
      (node (ref "U72") (pin "13") (pinfunction "IO19_13") (pintype "passive"))
    )
    (net (code "94") (name "unconnected-(U72-IO20-Pad14)") (class "Default")
      (node (ref "U72") (pin "14") (pinfunction "IO20_14") (pintype "passive"))
    )
    (net (code "95") (name "unconnected-(U72-IO21-Pad23)") (class "Default")
      (node (ref "U72") (pin "23") (pinfunction "IO21_23") (pintype "passive"))
    )
    (net (code "96") (name "unconnected-(U72-IO35-Pad28)") (class "Default")
      (node (ref "U72") (pin "28") (pinfunction "IO35_28") (pintype "passive"))
    )
    (net (code "97") (name "unconnected-(U72-IO36-Pad29)") (class "Default")
      (node (ref "U72") (pin "29") (pinfunction "IO36_29") (pintype "passive"))
    )
    (net (code "98") (name "unconnected-(U72-IO39-Pad32)") (class "Default")
      (node (ref "U72") (pin "32") (pinfunction "IO39_32") (pintype "passive"))
    )
    (net (code "99") (name "unconnected-(U72-IO40-Pad33)") (class "Default")
      (node (ref "U72") (pin "33") (pinfunction "IO40_33") (pintype "passive"))
    )
    (net (code "100") (name "unconnected-(U72-IO41-Pad34)") (class "Default")
      (node (ref "U72") (pin "34") (pinfunction "IO41_34") (pintype "passive"))
    )
    (net (code "101") (name "unconnected-(U72-IO42-Pad35)") (class "Default")
      (node (ref "U72") (pin "35") (pinfunction "IO42_35") (pintype "passive"))
    )
    (net (code "102") (name "unconnected-(U72-IO45-Pad26)") (class "Default")
      (node (ref "U72") (pin "26") (pinfunction "IO45_26") (pintype "passive"))
    )
    (net (code "103") (name "unconnected-(U72-IO47-Pad24)") (class "Default")
      (node (ref "U72") (pin "24") (pinfunction "IO47_24") (pintype "passive"))
    )
    (net (code "104") (name "unconnected-(U72-IO48-Pad25)") (class "Default")
      (node (ref "U72") (pin "25") (pinfunction "IO48_25") (pintype "passive"))
    )
    (net (code "105") (name "unconnected-(U72-RXD0-Pad36)") (class "Default")
      (node (ref "U72") (pin "36") (pinfunction "RXD0_36") (pintype "passive"))
    )
    (net (code "106") (name "unconnected-(U72-TXD0-Pad37)") (class "Default")
      (node (ref "U72") (pin "37") (pinfunction "TXD0_37") (pintype "passive"))
    )
  )
)
